# Blimp_Control_V0_3.net
KiCad netlist of a schematic drawn in EAGLE
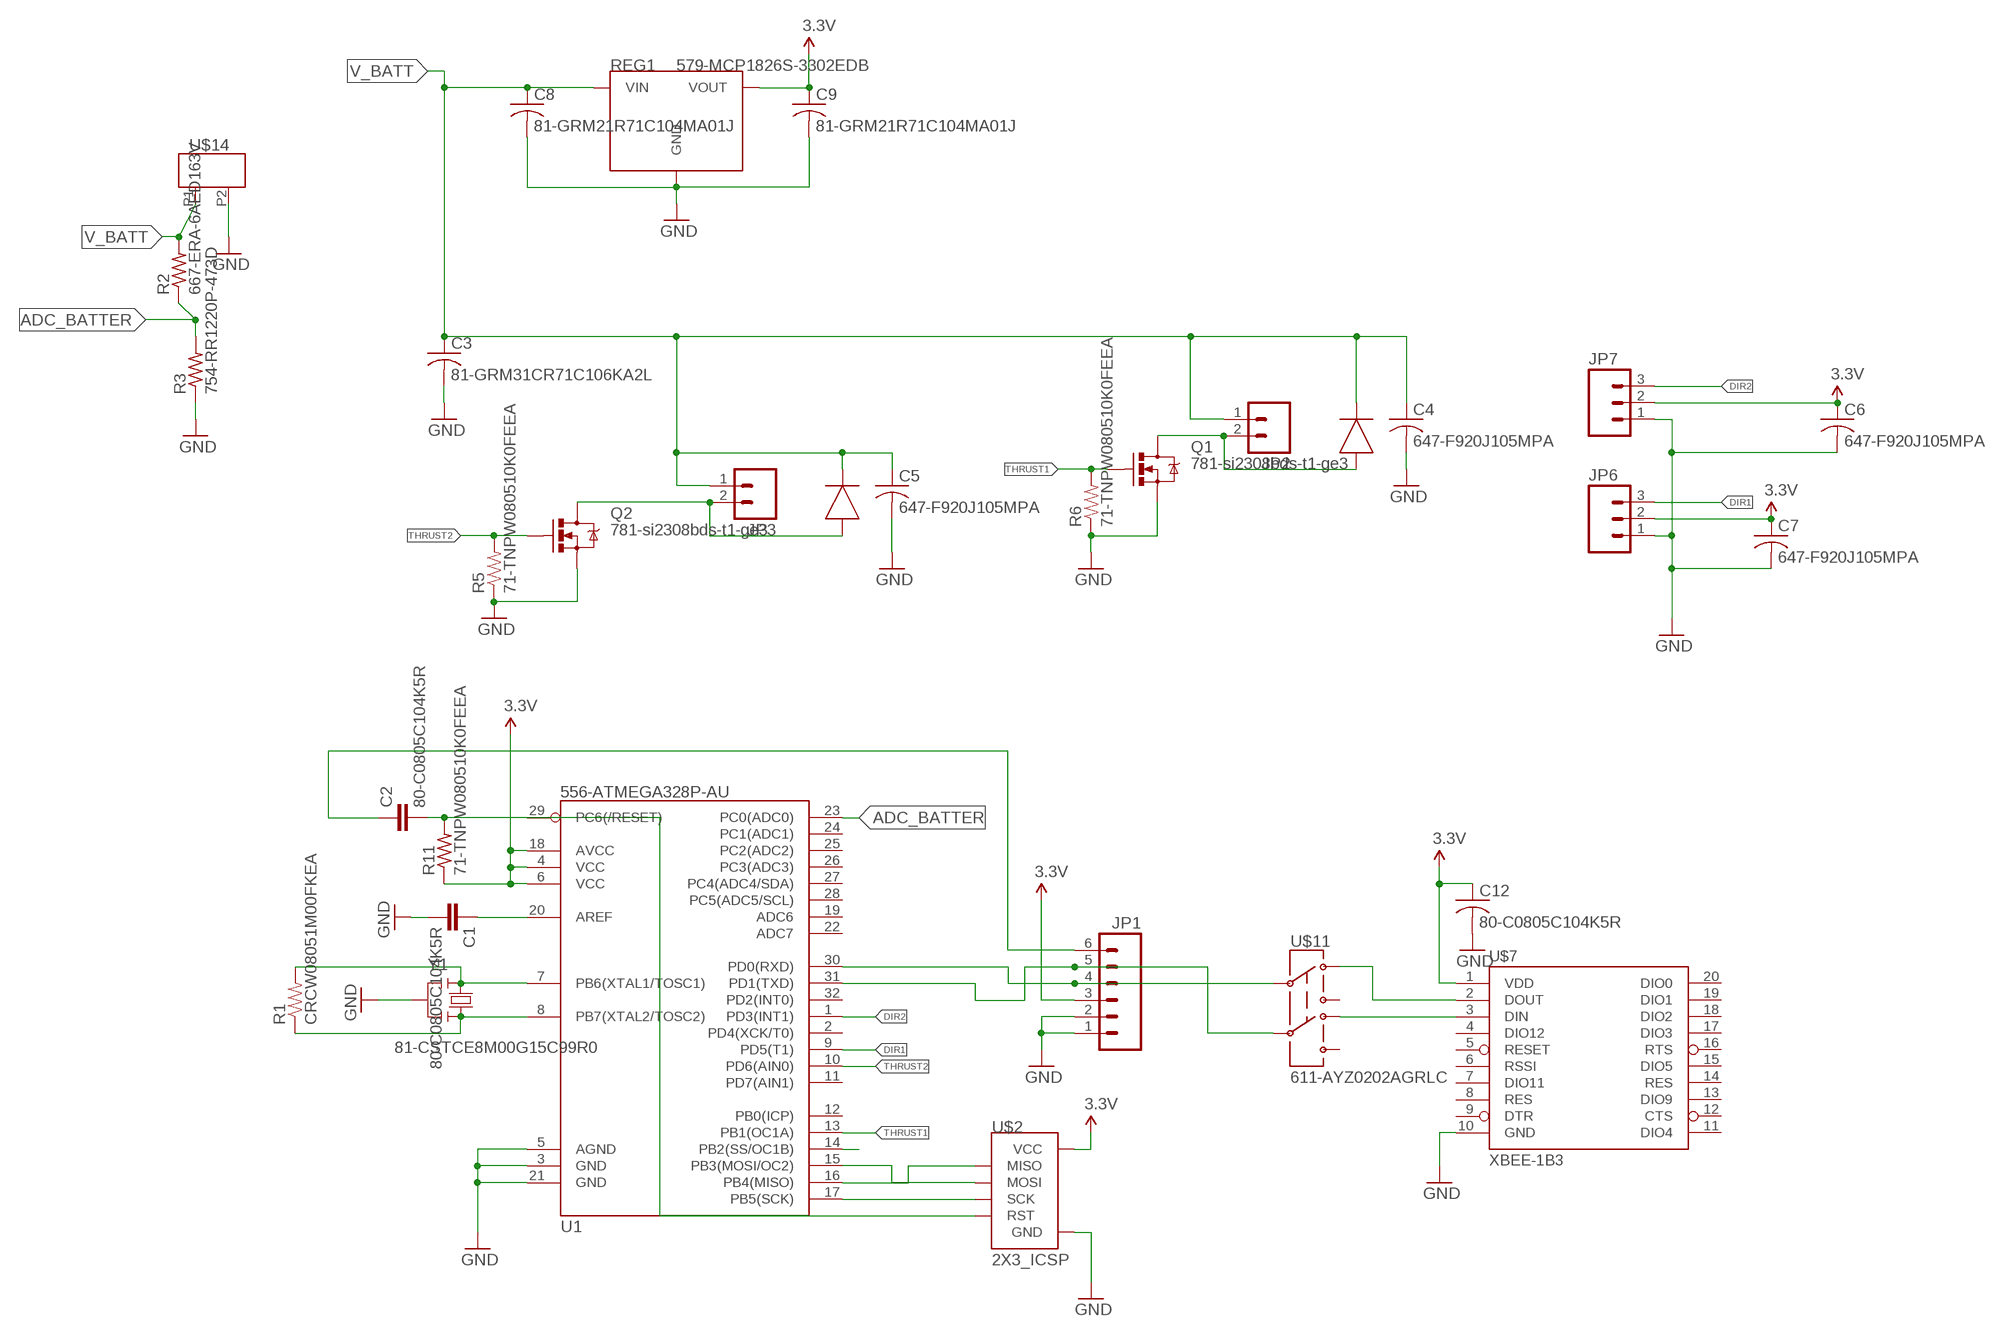
[diagram p0: schematic, sheet 1]

(export (version "E")
  (design (tool "Eeschema 10.0.6"))
  (components
    (comp (ref "C1")
      (value "80-C0805C104K5R")
      (footprint "eagle-import:0805")
      (libsource (lib "eagle-import") (part "CAP0805"))
    )
    (comp (ref "C2")
      (value "80-C0805C104K5R")
      (footprint "eagle-import:0805")
      (libsource (lib "eagle-import") (part "CAP0805"))
    )
    (comp (ref "C3")
      (value "81-GRM31CR71C106KA2L")
      (footprint "eagle-import:C1206")
      (libsource (lib "eagle-import") (part "C-USC1206"))
    )
    (comp (ref "C4")
      (value "647-F920J105MPA")
      (footprint "eagle-import:C0805")
      (libsource (lib "eagle-import") (part "C-USC0805"))
    )
    (comp (ref "C5")
      (value "647-F920J105MPA")
      (footprint "eagle-import:C0805")
      (libsource (lib "eagle-import") (part "C-USC0805"))
    )
    (comp (ref "C6")
      (value "647-F920J105MPA")
      (footprint "eagle-import:C0805")
      (libsource (lib "eagle-import") (part "C-USC0805"))
    )
    (comp (ref "C7")
      (value "647-F920J105MPA")
      (footprint "eagle-import:C0805")
      (libsource (lib "eagle-import") (part "C-USC0805"))
    )
    (comp (ref "C8")
      (value "81-GRM21R71C104MA01J")
      (footprint "eagle-import:C0805")
      (libsource (lib "eagle-import") (part "C-USC0805"))
    )
    (comp (ref "C9")
      (value "81-GRM21R71C104MA01J")
      (footprint "eagle-import:C0805")
      (libsource (lib "eagle-import") (part "C-USC0805"))
    )
    (comp (ref "C12")
      (value "80-C0805C104K5R")
      (footprint "eagle-import:C0805")
      (libsource (lib "eagle-import") (part "C-USC0805"))
    )
    (comp (ref "D1")
      (value "621-SBR07U20LPS-7")
      (footprint "eagle-import:X2-DFN1006-2")
      (libsource (lib "eagle-import") (part "DIODESBR07U20LPS"))
    )
    (comp (ref "D2")
      (value "621-SBR07U20LPS-7")
      (footprint "eagle-import:X2-DFN1006-2")
      (libsource (lib "eagle-import") (part "DIODESBR07U20LPS"))
    )
    (comp (ref "JP1")
      (value "M06LOCK")
      (footprint "eagle-import:1X06_LOCK")
      (libsource (lib "eagle-import") (part "M06LOCK"))
    )
    (comp (ref "JP2")
      (value "M02PTH")
      (footprint "eagle-import:1X02")
      (libsource (lib "eagle-import") (part "M02PTH"))
    )
    (comp (ref "JP3")
      (value "M02PTH")
      (footprint "eagle-import:1X02")
      (libsource (lib "eagle-import") (part "M02PTH"))
    )
    (comp (ref "JP6")
      (value "M03LOCK")
      (footprint "eagle-import:1X03_LOCK")
      (libsource (lib "eagle-import") (part "M03LOCK"))
    )
    (comp (ref "JP7")
      (value "M03LOCK")
      (footprint "eagle-import:1X03_LOCK")
      (libsource (lib "eagle-import") (part "M03LOCK"))
    )
    (comp (ref "Q1")
      (value "781-si2308bds-t1-ge3")
      (footprint "eagle-import:SOT23-3")
      (libsource (lib "eagle-import") (part "MOSFET-NCHANNELSMD"))
    )
    (comp (ref "Q2")
      (value "781-si2308bds-t1-ge3")
      (footprint "eagle-import:SOT23-3")
      (libsource (lib "eagle-import") (part "MOSFET-NCHANNELSMD"))
    )
    (comp (ref "R1")
      (value "CRCW08051M00FKEA")
      (footprint "eagle-import:0805")
      (libsource (lib "eagle-import") (part "RESISTOR"))
    )
    (comp (ref "R2")
      (value "667-ERA-6AED163V")
      (footprint "eagle-import:R0805")
      (libsource (lib "eagle-import") (part "R-US_R0805"))
    )
    (comp (ref "R3")
      (value "754-RR1220P-473D")
      (footprint "eagle-import:R0805")
      (libsource (lib "eagle-import") (part "R-US_R0805"))
    )
    (comp (ref "R5")
      (value "71-TNPW080510K0FEEA")
      (footprint "eagle-import:0805")
      (libsource (lib "eagle-import") (part "RESISTOR"))
    )
    (comp (ref "R6")
      (value "71-TNPW080510K0FEEA")
      (footprint "eagle-import:0805")
      (libsource (lib "eagle-import") (part "RESISTOR"))
    )
    (comp (ref "R11")
      (value "71-TNPW080510K0FEEA")
      (footprint "eagle-import:R0805")
      (libsource (lib "eagle-import") (part "R-US_R0805"))
    )
    (comp (ref "REG1")
      (value "579-MCP1826S-3302EDB")
      (footprint "eagle-import:SOT-223-3")
      (libsource (lib "eagle-import") (part "LDO_3_PORTMCP1826S"))
    )
    (comp (ref "U$2")
      (value "2X3_ICSP")
      (footprint "eagle-import:2X3_ICSP")
      (libsource (lib "eagle-import") (part "2X3_ICSP"))
    )
    (comp (ref "U$7")
      (value "XBEE-1B3")
      (footprint "eagle-import:XBEE-SMD")
      (libsource (lib "eagle-import") (part "XBEE-1B3"))
    )
    (comp (ref "U$11")
      (value "611-AYZ0202AGRLC")
      (footprint "eagle-import:AYZ0202")
      (libsource (lib "eagle-import") (part "SWITCH-DPDTSMD"))
    )
    (comp (ref "U$14")
      (value "538-53047-0210")
      (footprint "eagle-import:MOLEX_2POLE_PICO")
      (libsource (lib "eagle-import") (part "MOLEX_2POLE_PICO"))
    )
    (comp (ref "U1")
      (value "556-ATMEGA328P-AU")
      (footprint "eagle-import:TQFP32-08")
      (libsource (lib "eagle-import") (part "ATMEGA168"))
    )
    (comp (ref "Y1")
      (value "81-CSTCE8M00G15C99R0")
      (footprint "eagle-import:RESONATOR")
      (libsource (lib "eagle-import") (part "RESONATORMU"))
    )
  )
  (nets
    (net (code "1") (name "3.3V") (class "Default")
      (node (ref "C12") (pin "1") (pinfunction "1_1") (pintype "passive"))
      (node (ref "C6") (pin "1") (pinfunction "1_1") (pintype "passive"))
      (node (ref "C7") (pin "1") (pinfunction "1_1") (pintype "passive"))
      (node (ref "C9") (pin "1") (pinfunction "1_1") (pintype "passive"))
      (node (ref "JP1") (pin "3") (pinfunction "3_3") (pintype "passive"))
      (node (ref "JP6") (pin "2") (pinfunction "2_2") (pintype "passive"))
      (node (ref "JP7") (pin "2") (pinfunction "2_2") (pintype "passive"))
      (node (ref "R11") (pin "1") (pinfunction "1_1") (pintype "passive"))
      (node (ref "REG1") (pin "3") (pinfunction "VOUT_3") (pintype "bidirectional"))
      (node (ref "U$2") (pin "VCC") (pinfunction "VCC_VCC") (pintype "bidirectional"))
      (node (ref "U$7") (pin "1") (pinfunction "VDD_1") (pintype "power_in"))
      (node (ref "U1") (pin "18") (pinfunction "AVCC_18") (pintype "bidirectional"))
      (node (ref "U1") (pin "4") (pinfunction "VCC_4") (pintype "bidirectional"))
      (node (ref "U1") (pin "6") (pinfunction "VCC_6") (pintype "bidirectional"))
    )
    (net (code "2") (name "ADC_BATTER") (class "Default")
      (node (ref "R2") (pin "1") (pinfunction "1_1") (pintype "passive"))
      (node (ref "R3") (pin "2") (pinfunction "2_2") (pintype "passive"))
      (node (ref "U1") (pin "23") (pinfunction "PC0(ADC0)_23") (pintype "bidirectional"))
    )
    (net (code "3") (name "DIR1") (class "Default")
      (node (ref "JP6") (pin "3") (pinfunction "3_3") (pintype "passive"))
      (node (ref "U1") (pin "9") (pinfunction "PD5(T1)_9") (pintype "bidirectional"))
    )
    (net (code "4") (name "DIR2") (class "Default")
      (node (ref "JP7") (pin "3") (pinfunction "3_3") (pintype "passive"))
      (node (ref "U1") (pin "1") (pinfunction "PD3(INT1)_1") (pintype "bidirectional"))
    )
    (net (code "5") (name "GND") (class "Default")
      (node (ref "C1") (pin "2") (pinfunction "2_2") (pintype "passive"))
      (node (ref "C12") (pin "2") (pinfunction "2_2") (pintype "passive"))
      (node (ref "C3") (pin "2") (pinfunction "2_2") (pintype "passive"))
      (node (ref "C4") (pin "2") (pinfunction "2_2") (pintype "passive"))
      (node (ref "C5") (pin "2") (pinfunction "2_2") (pintype "passive"))
      (node (ref "C6") (pin "2") (pinfunction "2_2") (pintype "passive"))
      (node (ref "C7") (pin "2") (pinfunction "2_2") (pintype "passive"))
      (node (ref "C8") (pin "2") (pinfunction "2_2") (pintype "passive"))
      (node (ref "C9") (pin "2") (pinfunction "2_2") (pintype "passive"))
      (node (ref "JP1") (pin "1") (pinfunction "1_1") (pintype "passive"))
      (node (ref "JP1") (pin "2") (pinfunction "2_2") (pintype "passive"))
      (node (ref "JP6") (pin "1") (pinfunction "1_1") (pintype "passive"))
      (node (ref "JP7") (pin "1") (pinfunction "1_1") (pintype "passive"))
      (node (ref "Q1") (pin "2") (pinfunction "S_2") (pintype "passive"))
      (node (ref "Q2") (pin "2") (pinfunction "S_2") (pintype "passive"))
      (node (ref "R3") (pin "1") (pinfunction "1_1") (pintype "passive"))
      (node (ref "R5") (pin "1") (pinfunction "1_1") (pintype "passive"))
      (node (ref "R6") (pin "1") (pinfunction "1_1") (pintype "passive"))
      (node (ref "REG1") (pin "2") (pinfunction "GND_2") (pintype "bidirectional"))
      (node (ref "REG1") (pin "4") (pinfunction "GND_4") (pintype "bidirectional"))
      (node (ref "U$14") (pin "P2") (pinfunction "P2_P2") (pintype "bidirectional"))
      (node (ref "U$2") (pin "GND") (pinfunction "GND_GND") (pintype "bidirectional"))
      (node (ref "U$7") (pin "10") (pinfunction "GND_10") (pintype "power_in"))
      (node (ref "U1") (pin "21") (pinfunction "GND_21") (pintype "bidirectional"))
      (node (ref "U1") (pin "3") (pinfunction "GND_3") (pintype "bidirectional"))
      (node (ref "U1") (pin "5") (pinfunction "AGND_5") (pintype "bidirectional"))
      (node (ref "Y1") (pin "2") (pinfunction "2_2") (pintype "passive"))
    )
    (net (code "6") (name "Net-(C2-Pad1)") (class "Default")
      (node (ref "C2") (pin "1") (pinfunction "1_1") (pintype "passive"))
      (node (ref "JP1") (pin "6") (pinfunction "6_6") (pintype "passive"))
    )
    (net (code "7") (name "Net-(Q1-D)") (class "Default")
      (node (ref "D2") (pin "A") (pinfunction "A_A") (pintype "bidirectional"))
      (node (ref "JP2") (pin "2") (pinfunction "2_2") (pintype "passive"))
      (node (ref "Q1") (pin "3") (pinfunction "D_3") (pintype "passive"))
    )
    (net (code "8") (name "Net-(Q2-D)") (class "Default")
      (node (ref "D1") (pin "A") (pinfunction "A_A") (pintype "bidirectional"))
      (node (ref "JP3") (pin "2") (pinfunction "2_2") (pintype "passive"))
      (node (ref "Q2") (pin "3") (pinfunction "D_3") (pintype "passive"))
    )
    (net (code "9") (name "Net-(U$7-DIN)") (class "Default")
      (node (ref "U$11") (pin "4") (pinfunction "4_4") (pintype "bidirectional"))
      (node (ref "U$7") (pin "3") (pinfunction "DIN_3") (pintype "input"))
    )
    (net (code "10") (name "Net-(U$7-DOUT)") (class "Default")
      (node (ref "U$11") (pin "1") (pinfunction "1_1") (pintype "bidirectional"))
      (node (ref "U$7") (pin "2") (pinfunction "DOUT_2") (pintype "output"))
    )
    (net (code "11") (name "Net-(U1-AREF)") (class "Default")
      (node (ref "C1") (pin "1") (pinfunction "1_1") (pintype "passive"))
      (node (ref "U1") (pin "20") (pinfunction "AREF_20") (pintype "bidirectional"))
    )
    (net (code "12") (name "Net-(U1-PB3(MOSI{slash}OC2))") (class "Default")
      (node (ref "U$2") (pin "MOSI") (pinfunction "MOSI_MOSI") (pintype "bidirectional"))
      (node (ref "U1") (pin "15") (pinfunction "PB3(MOSI/OC2)_15") (pintype "bidirectional"))
    )
    (net (code "13") (name "Net-(U1-PB4(MISO))") (class "Default")
      (node (ref "U$2") (pin "MISO") (pinfunction "MISO_MISO") (pintype "bidirectional"))
      (node (ref "U1") (pin "16") (pinfunction "PB4(MISO)_16") (pintype "bidirectional"))
    )
    (net (code "14") (name "Net-(U1-PB5(SCK))") (class "Default")
      (node (ref "U$2") (pin "SCK") (pinfunction "SCK_SCK") (pintype "bidirectional"))
      (node (ref "U1") (pin "17") (pinfunction "PB5(SCK)_17") (pintype "bidirectional"))
    )
    (net (code "15") (name "Net-(U1-PB6(XTAL1{slash}TOSC1))") (class "Default")
      (node (ref "R1") (pin "2") (pinfunction "2_2") (pintype "passive"))
      (node (ref "U1") (pin "7") (pinfunction "PB6(XTAL1/TOSC1)_7") (pintype "bidirectional"))
      (node (ref "Y1") (pin "1") (pinfunction "1_1") (pintype "passive"))
    )
    (net (code "16") (name "Net-(U1-PB7(XTAL2{slash}TOSC2))") (class "Default")
      (node (ref "R1") (pin "1") (pinfunction "1_1") (pintype "passive"))
      (node (ref "U1") (pin "8") (pinfunction "PB7(XTAL2/TOSC2)_8") (pintype "bidirectional"))
      (node (ref "Y1") (pin "3") (pinfunction "3_3") (pintype "passive"))
    )
    (net (code "17") (name "Net-(U1-PC6({slash}RESET))") (class "Default")
      (node (ref "C2") (pin "2") (pinfunction "2_2") (pintype "passive"))
      (node (ref "R11") (pin "2") (pinfunction "2_2") (pintype "passive"))
      (node (ref "U$2") (pin "RST") (pinfunction "RST_RST") (pintype "bidirectional"))
      (node (ref "U1") (pin "29") (pinfunction "PC6(/RESET)_29") (pintype "bidirectional"))
    )
    (net (code "18") (name "Net-(U1-PD0(RXD))") (class "Default")
      (node (ref "JP1") (pin "4") (pinfunction "4_4") (pintype "passive"))
      (node (ref "U$11") (pin "2") (pinfunction "2_2") (pintype "bidirectional"))
      (node (ref "U1") (pin "30") (pinfunction "PD0(RXD)_30") (pintype "bidirectional"))
    )
    (net (code "19") (name "Net-(U1-PD1(TXD))") (class "Default")
      (node (ref "JP1") (pin "5") (pinfunction "5_5") (pintype "passive"))
      (node (ref "U$11") (pin "5") (pinfunction "5_5") (pintype "bidirectional"))
      (node (ref "U1") (pin "31") (pinfunction "PD1(TXD)_31") (pintype "bidirectional"))
    )
    (net (code "20") (name "THRUST1") (class "Default")
      (node (ref "Q1") (pin "1") (pinfunction "G_1") (pintype "passive"))
      (node (ref "R6") (pin "2") (pinfunction "2_2") (pintype "passive"))
      (node (ref "U1") (pin "13") (pinfunction "PB1(OC1A)_13") (pintype "bidirectional"))
    )
    (net (code "21") (name "THRUST2") (class "Default")
      (node (ref "Q2") (pin "1") (pinfunction "G_1") (pintype "passive"))
      (node (ref "R5") (pin "2") (pinfunction "2_2") (pintype "passive"))
      (node (ref "U1") (pin "10") (pinfunction "PD6(AIN0)_10") (pintype "bidirectional"))
    )
    (net (code "22") (name "V_BATT") (class "Default")
      (node (ref "C3") (pin "1") (pinfunction "1_1") (pintype "passive"))
      (node (ref "C4") (pin "1") (pinfunction "1_1") (pintype "passive"))
      (node (ref "C5") (pin "1") (pinfunction "1_1") (pintype "passive"))
      (node (ref "C8") (pin "1") (pinfunction "1_1") (pintype "passive"))
      (node (ref "D1") (pin "C") (pinfunction "C_C") (pintype "bidirectional"))
      (node (ref "D2") (pin "C") (pinfunction "C_C") (pintype "bidirectional"))
      (node (ref "JP2") (pin "1") (pinfunction "1_1") (pintype "passive"))
      (node (ref "JP3") (pin "1") (pinfunction "1_1") (pintype "passive"))
      (node (ref "R2") (pin "2") (pinfunction "2_2") (pintype "passive"))
      (node (ref "REG1") (pin "1") (pinfunction "VIN_1") (pintype "bidirectional"))
      (node (ref "U$14") (pin "P1") (pinfunction "P1_P1") (pintype "bidirectional"))
    )
    (net (code "23") (name "unconnected-(U$7-CTS-Pad12)") (class "Default")
      (node (ref "U$7") (pin "12") (pinfunction "CTS_12") (pintype "output"))
    )
    (net (code "24") (name "unconnected-(U$7-DIO0-Pad20)") (class "Default")
      (node (ref "U$7") (pin "20") (pinfunction "DIO0_20") (pintype "bidirectional"))
    )
    (net (code "25") (name "unconnected-(U$7-DIO1-Pad19)") (class "Default")
      (node (ref "U$7") (pin "19") (pinfunction "DIO1_19") (pintype "bidirectional"))
    )
    (net (code "26") (name "unconnected-(U$7-DIO2-Pad18)") (class "Default")
      (node (ref "U$7") (pin "18") (pinfunction "DIO2_18") (pintype "bidirectional"))
    )
    (net (code "27") (name "unconnected-(U$7-DIO3-Pad17)") (class "Default")
      (node (ref "U$7") (pin "17") (pinfunction "DIO3_17") (pintype "bidirectional"))
    )
    (net (code "28") (name "unconnected-(U$7-DIO4-Pad11)") (class "Default")
      (node (ref "U$7") (pin "11") (pinfunction "DIO4_11") (pintype "bidirectional"))
    )
    (net (code "29") (name "unconnected-(U$7-DIO5-Pad15)") (class "Default")
      (node (ref "U$7") (pin "15") (pinfunction "DIO5_15") (pintype "bidirectional"))
    )
    (net (code "30") (name "unconnected-(U$7-DIO9-Pad13)") (class "Default")
      (node (ref "U$7") (pin "13") (pinfunction "DIO9_13") (pintype "bidirectional"))
    )
    (net (code "31") (name "unconnected-(U$7-DIO11-Pad7)") (class "Default")
      (node (ref "U$7") (pin "7") (pinfunction "DIO11_7") (pintype "bidirectional"))
    )
    (net (code "32") (name "unconnected-(U$7-DIO12-Pad4)") (class "Default")
      (node (ref "U$7") (pin "4") (pinfunction "DIO12_4") (pintype "bidirectional"))
    )
    (net (code "33") (name "unconnected-(U$7-DTR-Pad9)") (class "Default")
      (node (ref "U$7") (pin "9") (pinfunction "DTR_9") (pintype "bidirectional"))
    )
    (net (code "34") (name "unconnected-(U$7-RES-Pad8)") (class "Default")
      (node (ref "U$7") (pin "8") (pinfunction "RES_8") (pintype "bidirectional"))
    )
    (net (code "35") (name "unconnected-(U$7-RES-Pad14)") (class "Default")
      (node (ref "U$7") (pin "14") (pinfunction "RES_14") (pintype "bidirectional"))
    )
    (net (code "36") (name "unconnected-(U$7-RESET-Pad5)") (class "Default")
      (node (ref "U$7") (pin "5") (pinfunction "RESET_5") (pintype "input"))
    )
    (net (code "37") (name "unconnected-(U$7-RSSI-Pad6)") (class "Default")
      (node (ref "U$7") (pin "6") (pinfunction "RSSI_6") (pintype "bidirectional"))
    )
    (net (code "38") (name "unconnected-(U$7-RTS-Pad16)") (class "Default")
      (node (ref "U$7") (pin "16") (pinfunction "RTS_16") (pintype "input"))
    )
    (net (code "39") (name "unconnected-(U$11-Pad3)") (class "Default")
      (node (ref "U$11") (pin "3") (pinfunction "3_3") (pintype "bidirectional"))
    )
    (net (code "40") (name "unconnected-(U$11-Pad6)") (class "Default")
      (node (ref "U$11") (pin "6") (pinfunction "6_6") (pintype "bidirectional"))
    )
    (net (code "41") (name "unconnected-(U1-ADC6-Pad19)") (class "Default")
      (node (ref "U1") (pin "19") (pinfunction "ADC6_19") (pintype "bidirectional"))
    )
    (net (code "42") (name "unconnected-(U1-ADC7-Pad22)") (class "Default")
      (node (ref "U1") (pin "22") (pinfunction "ADC7_22") (pintype "bidirectional"))
    )
    (net (code "43") (name "unconnected-(U1-PB0(ICP)-Pad12)") (class "Default")
      (node (ref "U1") (pin "12") (pinfunction "PB0(ICP)_12") (pintype "bidirectional"))
    )
    (net (code "44") (name "unconnected-(U1-PB2(SS{slash}OC1B)-Pad14)") (class "Default")
      (node (ref "U1") (pin "14") (pinfunction "PB2(SS/OC1B)_14") (pintype "bidirectional"))
    )
    (net (code "45") (name "unconnected-(U1-PC1(ADC1)-Pad24)") (class "Default")
      (node (ref "U1") (pin "24") (pinfunction "PC1(ADC1)_24") (pintype "bidirectional"))
    )
    (net (code "46") (name "unconnected-(U1-PC2(ADC2)-Pad25)") (class "Default")
      (node (ref "U1") (pin "25") (pinfunction "PC2(ADC2)_25") (pintype "bidirectional"))
    )
    (net (code "47") (name "unconnected-(U1-PC3(ADC3)-Pad26)") (class "Default")
      (node (ref "U1") (pin "26") (pinfunction "PC3(ADC3)_26") (pintype "bidirectional"))
    )
    (net (code "48") (name "unconnected-(U1-PC4(ADC4{slash}SDA)-Pad27)") (class "Default")
      (node (ref "U1") (pin "27") (pinfunction "PC4(ADC4/SDA)_27") (pintype "bidirectional"))
    )
    (net (code "49") (name "unconnected-(U1-PC5(ADC5{slash}SCL)-Pad28)") (class "Default")
      (node (ref "U1") (pin "28") (pinfunction "PC5(ADC5/SCL)_28") (pintype "bidirectional"))
    )
    (net (code "50") (name "unconnected-(U1-PD2(INT0)-Pad32)") (class "Default")
      (node (ref "U1") (pin "32") (pinfunction "PD2(INT0)_32") (pintype "bidirectional"))
    )
    (net (code "51") (name "unconnected-(U1-PD4(XCK{slash}T0)-Pad2)") (class "Default")
      (node (ref "U1") (pin "2") (pinfunction "PD4(XCK/T0)_2") (pintype "bidirectional"))
    )
    (net (code "52") (name "unconnected-(U1-PD7(AIN1)-Pad11)") (class "Default")
      (node (ref "U1") (pin "11") (pinfunction "PD7(AIN1)_11") (pintype "bidirectional"))
    )
  )
)
